# IO-Ports_1.net
KiCad netlist of a schematic drawn in Altium Designer
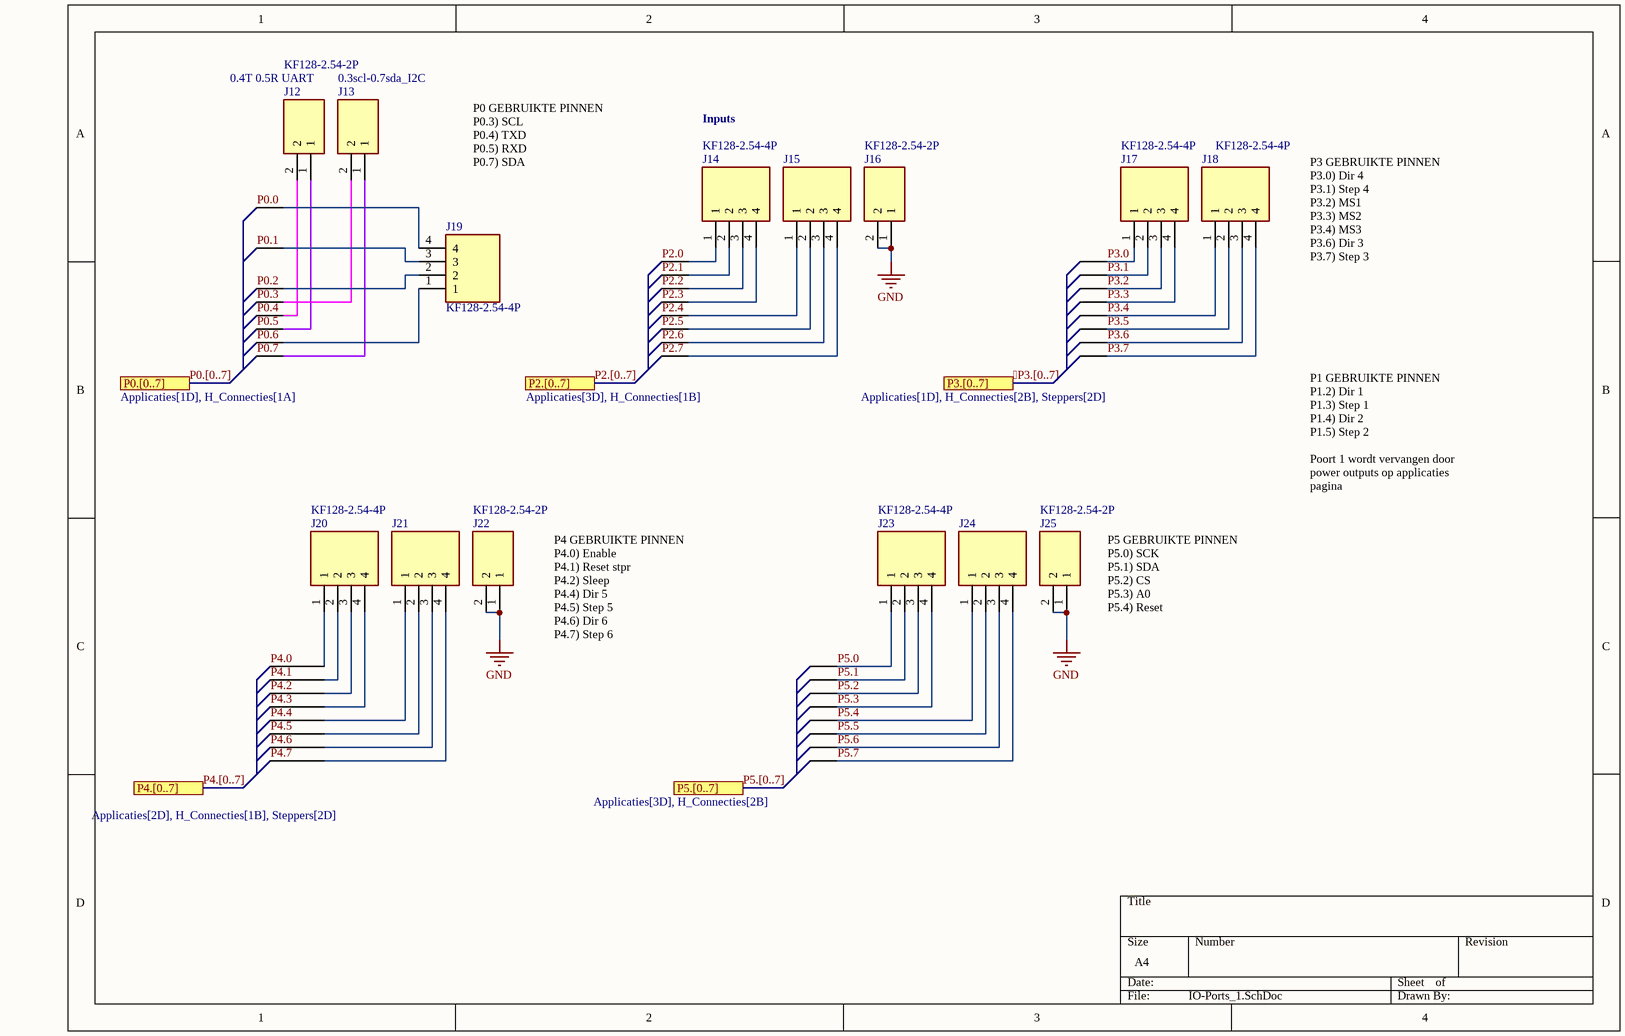
[diagram p0: IO-Ports_1.SchDoc]

(export (version "E")
  (design (tool "Eeschema 10.0.6"))
  (components
    (comp (ref "J12")
      (value "KF128-2.54-2P")
      (footprint "KF128-2.54-2P")
      (description "Connector")
      (libsource (lib "*") (part "KF128-2.54-2P"))
    )
    (comp (ref "J13")
      (value "~")
      (footprint "KF128-2.54-2P")
      (description "Connector")
      (fields (field (name "MANUFACTURER_PART_NUMBER") "KF128-2.54-2P"))
      (libsource (lib "*") (part "KF128-2.54-2P"))
    )
    (comp (ref "J14")
      (value "KF128-2.54-4P")
      (footprint "KF128-2.54-4P")
      (description "Connector")
      (libsource (lib "*") (part "KF128-2.54-4P"))
    )
    (comp (ref "J15")
      (value "~")
      (footprint "KF128-2.54-4P")
      (description "Connector")
      (fields (field (name "MANUFACTURER_PART_NUMBER") "KF128-2.54-4P"))
      (libsource (lib "*") (part "KF128-2.54-4P"))
    )
    (comp (ref "J16")
      (value "KF128-2.54-2P")
      (footprint "KF128-2.54-2P")
      (description "Connector")
      (libsource (lib "*") (part "KF128-2.54-2P"))
    )
    (comp (ref "J17")
      (value "KF128-2.54-4P")
      (footprint "KF128-2.54-4P")
      (description "Connector")
      (libsource (lib "*") (part "KF128-2.54-4P"))
    )
    (comp (ref "J18")
      (value "KF128-2.54-4P")
      (footprint "KF128-2.54-4P")
      (description "Connector")
      (libsource (lib "*") (part "KF128-2.54-4P"))
    )
    (comp (ref "J19")
      (value "KF128-2.54-4P")
      (footprint "KF128-2.54-4P")
      (description "Connector")
      (libsource (lib "*") (part "KF128-2.54-4P"))
    )
    (comp (ref "J20")
      (value "KF128-2.54-4P")
      (footprint "KF128-2.54-4P")
      (description "Connector")
      (libsource (lib "*") (part "KF128-2.54-4P"))
    )
    (comp (ref "J21")
      (value "~")
      (footprint "KF128-2.54-4P")
      (description "Connector")
      (fields (field (name "MANUFACTURER_PART_NUMBER") "KF128-2.54-4P"))
      (libsource (lib "*") (part "KF128-2.54-4P"))
    )
    (comp (ref "J22")
      (value "KF128-2.54-2P")
      (footprint "KF128-2.54-2P")
      (description "Connector")
      (libsource (lib "*") (part "KF128-2.54-2P"))
    )
    (comp (ref "J23")
      (value "KF128-2.54-4P")
      (footprint "KF128-2.54-4P")
      (description "Connector")
      (libsource (lib "*") (part "KF128-2.54-4P"))
    )
    (comp (ref "J24")
      (value "~")
      (footprint "KF128-2.54-4P")
      (description "Connector")
      (fields (field (name "MANUFACTURER_PART_NUMBER") "KF128-2.54-4P"))
      (libsource (lib "*") (part "KF128-2.54-4P"))
    )
    (comp (ref "J25")
      (value "KF128-2.54-2P")
      (footprint "KF128-2.54-2P")
      (description "Connector")
      (libsource (lib "*") (part "KF128-2.54-2P"))
    )
  )
  (nets
    (net (code "9") (name "/P3.0") (class "Default")
      (node (ref "J17") (pin "1") (pinfunction "1_1") (pintype "passive"))
    )
    (net (code "10") (name "/P3.1") (class "Default")
      (node (ref "J17") (pin "2") (pinfunction "2_2") (pintype "passive"))
    )
    (net (code "11") (name "/P3.2") (class "Default")
      (node (ref "J17") (pin "3") (pinfunction "3_3") (pintype "passive"))
    )
    (net (code "12") (name "/P3.3") (class "Default")
      (node (ref "J17") (pin "4") (pinfunction "4_4") (pintype "passive"))
    )
    (net (code "13") (name "/P3.4") (class "Default")
      (node (ref "J18") (pin "1") (pinfunction "1_1") (pintype "passive"))
    )
    (net (code "14") (name "/P3.5") (class "Default")
      (node (ref "J18") (pin "2") (pinfunction "2_2") (pintype "passive"))
    )
    (net (code "15") (name "/P3.6") (class "Default")
      (node (ref "J18") (pin "3") (pinfunction "3_3") (pintype "passive"))
    )
    (net (code "16") (name "/P3.7") (class "Default")
      (node (ref "J18") (pin "4") (pinfunction "4_4") (pintype "passive"))
    )
    (net (code "18") (name "/P0.0") (class "Default")
      (node (ref "J19") (pin "4") (pinfunction "4_4") (pintype "passive"))
    )
    (net (code "19") (name "/P0.1") (class "Default")
      (node (ref "J19") (pin "3") (pinfunction "3_3") (pintype "passive"))
    )
    (net (code "20") (name "/P0.2") (class "Default")
      (node (ref "J19") (pin "2") (pinfunction "2_2") (pintype "passive"))
    )
    (net (code "21") (name "/P0.3") (class "Default")
      (node (ref "J13") (pin "2") (pinfunction "2_2") (pintype "passive"))
    )
    (net (code "22") (name "/P0.4") (class "Default")
      (node (ref "J12") (pin "2") (pinfunction "2_2") (pintype "passive"))
    )
    (net (code "23") (name "/P0.5") (class "Default")
      (node (ref "J12") (pin "1") (pinfunction "1_1") (pintype "passive"))
    )
    (net (code "24") (name "/P0.6") (class "Default")
      (node (ref "J19") (pin "1") (pinfunction "1_1") (pintype "passive"))
    )
    (net (code "25") (name "/P0.7") (class "Default")
      (node (ref "J13") (pin "1") (pinfunction "1_1") (pintype "passive"))
    )
    (net (code "27") (name "/P2.0") (class "Default")
      (node (ref "J14") (pin "1") (pinfunction "1_1") (pintype "passive"))
    )
    (net (code "28") (name "/P2.1") (class "Default")
      (node (ref "J14") (pin "2") (pinfunction "2_2") (pintype "passive"))
    )
    (net (code "29") (name "/P2.2") (class "Default")
      (node (ref "J14") (pin "3") (pinfunction "3_3") (pintype "passive"))
    )
    (net (code "30") (name "/P2.3") (class "Default")
      (node (ref "J14") (pin "4") (pinfunction "4_4") (pintype "passive"))
    )
    (net (code "31") (name "/P2.4") (class "Default")
      (node (ref "J15") (pin "1") (pinfunction "1_1") (pintype "passive"))
    )
    (net (code "32") (name "/P2.5") (class "Default")
      (node (ref "J15") (pin "2") (pinfunction "2_2") (pintype "passive"))
    )
    (net (code "33") (name "/P2.6") (class "Default")
      (node (ref "J15") (pin "3") (pinfunction "3_3") (pintype "passive"))
    )
    (net (code "34") (name "/P2.7") (class "Default")
      (node (ref "J15") (pin "4") (pinfunction "4_4") (pintype "passive"))
    )
    (net (code "36") (name "/P4.0") (class "Default")
      (node (ref "J20") (pin "1") (pinfunction "1_1") (pintype "passive"))
    )
    (net (code "37") (name "/P4.1") (class "Default")
      (node (ref "J20") (pin "2") (pinfunction "2_2") (pintype "passive"))
    )
    (net (code "38") (name "/P4.2") (class "Default")
      (node (ref "J20") (pin "3") (pinfunction "3_3") (pintype "passive"))
    )
    (net (code "39") (name "/P4.3") (class "Default")
      (node (ref "J20") (pin "4") (pinfunction "4_4") (pintype "passive"))
    )
    (net (code "40") (name "/P4.4") (class "Default")
      (node (ref "J21") (pin "1") (pinfunction "1_1") (pintype "passive"))
    )
    (net (code "41") (name "/P4.5") (class "Default")
      (node (ref "J21") (pin "2") (pinfunction "2_2") (pintype "passive"))
    )
    (net (code "42") (name "/P4.6") (class "Default")
      (node (ref "J21") (pin "3") (pinfunction "3_3") (pintype "passive"))
    )
    (net (code "43") (name "/P4.7") (class "Default")
      (node (ref "J21") (pin "4") (pinfunction "4_4") (pintype "passive"))
    )
    (net (code "45") (name "/P5.0") (class "Default")
      (node (ref "J23") (pin "1") (pinfunction "1_1") (pintype "passive"))
    )
    (net (code "46") (name "/P5.1") (class "Default")
      (node (ref "J23") (pin "2") (pinfunction "2_2") (pintype "passive"))
    )
    (net (code "47") (name "/P5.2") (class "Default")
      (node (ref "J23") (pin "3") (pinfunction "3_3") (pintype "passive"))
    )
    (net (code "48") (name "/P5.3") (class "Default")
      (node (ref "J23") (pin "4") (pinfunction "4_4") (pintype "passive"))
    )
    (net (code "49") (name "/P5.4") (class "Default")
      (node (ref "J24") (pin "1") (pinfunction "1_1") (pintype "passive"))
    )
    (net (code "50") (name "/P5.5") (class "Default")
      (node (ref "J24") (pin "2") (pinfunction "2_2") (pintype "passive"))
    )
    (net (code "51") (name "/P5.6") (class "Default")
      (node (ref "J24") (pin "3") (pinfunction "3_3") (pintype "passive"))
    )
    (net (code "52") (name "/P5.7") (class "Default")
      (node (ref "J24") (pin "4") (pinfunction "4_4") (pintype "passive"))
    )
    (net (code "54") (name "GND") (class "Default")
      (node (ref "J16") (pin "1") (pinfunction "1_1") (pintype "passive"))
      (node (ref "J16") (pin "2") (pinfunction "2_2") (pintype "passive"))
      (node (ref "J22") (pin "1") (pinfunction "1_1") (pintype "passive"))
      (node (ref "J22") (pin "2") (pinfunction "2_2") (pintype "passive"))
      (node (ref "J25") (pin "1") (pinfunction "1_1") (pintype "passive"))
      (node (ref "J25") (pin "2") (pinfunction "2_2") (pintype "passive"))
    )
  )
)
